# povduino.net
KiCad netlist of a schematic drawn in EAGLE
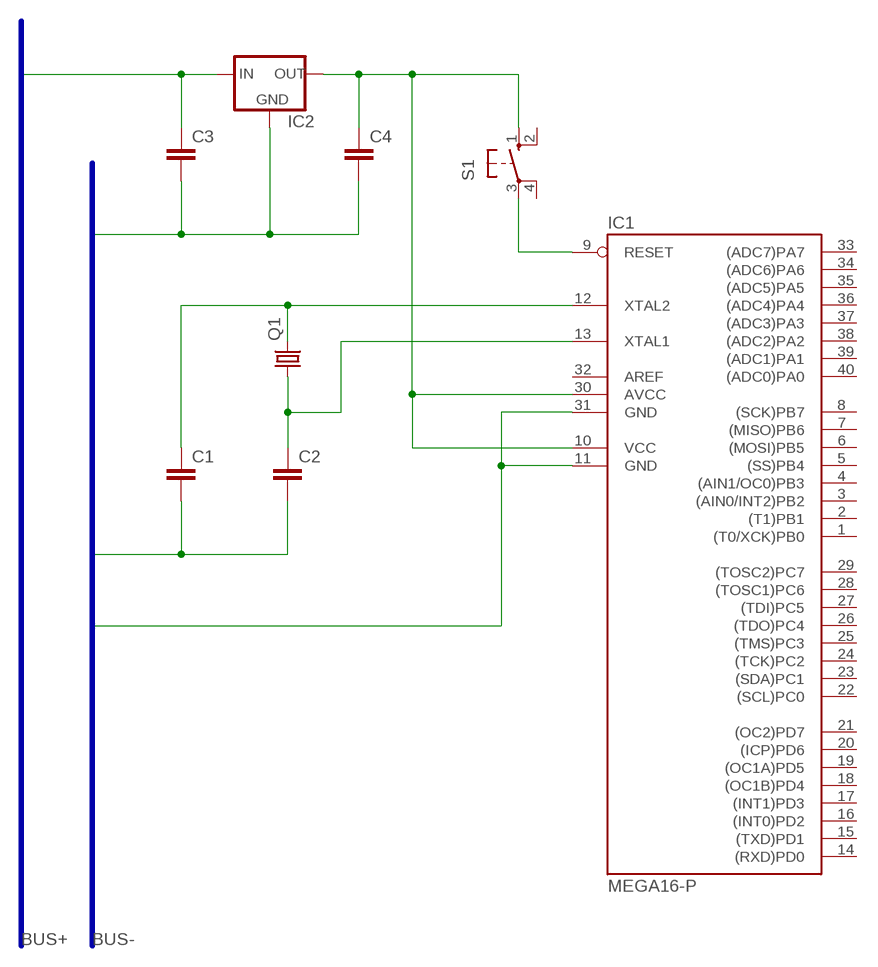
[diagram p0: schematic, sheet 1]

(export (version "E")
  (design (tool "Eeschema 10.0.6"))
  (components
    (comp (ref "C1")
      (value "C-EU025-025X050")
      (footprint "eagle-import:C025-025X050")
      (libsource (lib "eagle-import") (part "C-EU025-025X050"))
    )
    (comp (ref "C2")
      (value "C-EU025-025X050")
      (footprint "eagle-import:C025-025X050")
      (libsource (lib "eagle-import") (part "C-EU025-025X050"))
    )
    (comp (ref "C3")
      (value "C-EU025-025X050")
      (footprint "eagle-import:C025-025X050")
      (libsource (lib "eagle-import") (part "C-EU025-025X050"))
    )
    (comp (ref "C4")
      (value "C-EU025-025X050")
      (footprint "eagle-import:C025-025X050")
      (libsource (lib "eagle-import") (part "C-EU025-025X050"))
    )
    (comp (ref "IC1")
      (value "MEGA16-P")
      (footprint "eagle-import:DIL40")
      (fields (field (name "MPN") "ATMEGA16-16PU"))
      (libsource (lib "eagle-import") (part "MEGA16-P"))
    )
    (comp (ref "IC2")
      (value "78XXL")
      (footprint "eagle-import:78XXL")
      (libsource (lib "eagle-import") (part "78XXL"))
    )
    (comp (ref "Q1")
      (value "CRYSTALHC49S")
      (footprint "eagle-import:HC49_S")
      (libsource (lib "eagle-import") (part "CRYSTALHC49S"))
    )
    (comp (ref "S1")
      (value "10-XX")
      (footprint "eagle-import:B3F-10XX")
      (fields (field (name "MPN") "B3F-1000"))
      (libsource (lib "eagle-import") (part "10-XX"))
    )
  )
  (nets
    (net (code "1") (name "/BUS+") (class "Default")
      (node (ref "C3") (pin "1") (pinfunction "1_1") (pintype "passive"))
      (node (ref "C4") (pin "1") (pinfunction "1_1") (pintype "passive"))
      (node (ref "IC1") (pin "10") (pinfunction "VCC_10") (pintype "power_in"))
      (node (ref "IC1") (pin "30") (pinfunction "AVCC_30") (pintype "power_in"))
      (node (ref "IC2") (pin "IN") (pinfunction "IN_IN") (pintype "input"))
      (node (ref "IC2") (pin "OUT") (pinfunction "OUT_OUT") (pintype "passive"))
      (node (ref "S1") (pin "1") (pinfunction "S_1") (pintype "passive"))
    )
    (net (code "2") (name "/BUS-") (class "Default")
      (node (ref "C3") (pin "2") (pinfunction "2_2") (pintype "passive"))
      (node (ref "C4") (pin "2") (pinfunction "2_2") (pintype "passive"))
      (node (ref "IC1") (pin "11") (pinfunction "GND_11") (pintype "power_in"))
      (node (ref "IC1") (pin "31") (pinfunction "GND_31") (pintype "power_in"))
      (node (ref "IC2") (pin "GND") (pinfunction "GND_GND") (pintype "input"))
    )
    (net (code "5") (name "Net-(C1-Pad2)") (class "Default")
      (node (ref "C1") (pin "2") (pinfunction "2_2") (pintype "passive"))
      (node (ref "C2") (pin "2") (pinfunction "2_2") (pintype "passive"))
    )
    (net (code "6") (name "Net-(IC1-RESET)") (class "Default")
      (node (ref "IC1") (pin "9") (pinfunction "RESET_9") (pintype "input"))
      (node (ref "S1") (pin "3") (pinfunction "P_3") (pintype "passive"))
    )
    (net (code "7") (name "Net-(IC1-XTAL1)") (class "Default")
      (node (ref "C2") (pin "1") (pinfunction "1_1") (pintype "passive"))
      (node (ref "IC1") (pin "13") (pinfunction "XTAL1_13") (pintype "bidirectional"))
      (node (ref "Q1") (pin "1") (pinfunction "1_1") (pintype "passive"))
    )
    (net (code "8") (name "Net-(IC1-XTAL2)") (class "Default")
      (node (ref "C1") (pin "1") (pinfunction "1_1") (pintype "passive"))
      (node (ref "IC1") (pin "12") (pinfunction "XTAL2_12") (pintype "bidirectional"))
      (node (ref "Q1") (pin "2") (pinfunction "2_2") (pintype "passive"))
    )
    (net (code "9") (name "unconnected-(IC1-(ADC0)PA0-Pad40)") (class "Default")
      (node (ref "IC1") (pin "40") (pinfunction "(ADC0)PA0_40") (pintype "bidirectional"))
    )
    (net (code "10") (name "unconnected-(IC1-(ADC1)PA1-Pad39)") (class "Default")
      (node (ref "IC1") (pin "39") (pinfunction "(ADC1)PA1_39") (pintype "bidirectional"))
    )
    (net (code "11") (name "unconnected-(IC1-(ADC2)PA2-Pad38)") (class "Default")
      (node (ref "IC1") (pin "38") (pinfunction "(ADC2)PA2_38") (pintype "bidirectional"))
    )
    (net (code "12") (name "unconnected-(IC1-(ADC3)PA3-Pad37)") (class "Default")
      (node (ref "IC1") (pin "37") (pinfunction "(ADC3)PA3_37") (pintype "bidirectional"))
    )
    (net (code "13") (name "unconnected-(IC1-(ADC4)PA4-Pad36)") (class "Default")
      (node (ref "IC1") (pin "36") (pinfunction "(ADC4)PA4_36") (pintype "bidirectional"))
    )
    (net (code "14") (name "unconnected-(IC1-(ADC5)PA5-Pad35)") (class "Default")
      (node (ref "IC1") (pin "35") (pinfunction "(ADC5)PA5_35") (pintype "bidirectional"))
    )
    (net (code "15") (name "unconnected-(IC1-(ADC6)PA6-Pad34)") (class "Default")
      (node (ref "IC1") (pin "34") (pinfunction "(ADC6)PA6_34") (pintype "bidirectional"))
    )
    (net (code "16") (name "unconnected-(IC1-(ADC7)PA7-Pad33)") (class "Default")
      (node (ref "IC1") (pin "33") (pinfunction "(ADC7)PA7_33") (pintype "bidirectional"))
    )
    (net (code "17") (name "unconnected-(IC1-(AIN0{slash}INT2)PB2-Pad3)") (class "Default")
      (node (ref "IC1") (pin "3") (pinfunction "(AIN0/INT2)PB2_3") (pintype "bidirectional"))
    )
    (net (code "18") (name "unconnected-(IC1-(AIN1{slash}OC0)PB3-Pad4)") (class "Default")
      (node (ref "IC1") (pin "4") (pinfunction "(AIN1/OC0)PB3_4") (pintype "bidirectional"))
    )
    (net (code "19") (name "unconnected-(IC1-(ICP)PD6-Pad20)") (class "Default")
      (node (ref "IC1") (pin "20") (pinfunction "(ICP)PD6_20") (pintype "bidirectional"))
    )
    (net (code "20") (name "unconnected-(IC1-(INT0)PD2-Pad16)") (class "Default")
      (node (ref "IC1") (pin "16") (pinfunction "(INT0)PD2_16") (pintype "bidirectional"))
    )
    (net (code "21") (name "unconnected-(IC1-(INT1)PD3-Pad17)") (class "Default")
      (node (ref "IC1") (pin "17") (pinfunction "(INT1)PD3_17") (pintype "bidirectional"))
    )
    (net (code "22") (name "unconnected-(IC1-(MISO)PB6-Pad7)") (class "Default")
      (node (ref "IC1") (pin "7") (pinfunction "(MISO)PB6_7") (pintype "bidirectional"))
    )
    (net (code "23") (name "unconnected-(IC1-(MOSI)PB5-Pad6)") (class "Default")
      (node (ref "IC1") (pin "6") (pinfunction "(MOSI)PB5_6") (pintype "bidirectional"))
    )
    (net (code "24") (name "unconnected-(IC1-(OC1A)PD5-Pad19)") (class "Default")
      (node (ref "IC1") (pin "19") (pinfunction "(OC1A)PD5_19") (pintype "bidirectional"))
    )
    (net (code "25") (name "unconnected-(IC1-(OC1B)PD4-Pad18)") (class "Default")
      (node (ref "IC1") (pin "18") (pinfunction "(OC1B)PD4_18") (pintype "bidirectional"))
    )
    (net (code "26") (name "unconnected-(IC1-(OC2)PD7-Pad21)") (class "Default")
      (node (ref "IC1") (pin "21") (pinfunction "(OC2)PD7_21") (pintype "bidirectional"))
    )
    (net (code "27") (name "unconnected-(IC1-(RXD)PD0-Pad14)") (class "Default")
      (node (ref "IC1") (pin "14") (pinfunction "(RXD)PD0_14") (pintype "bidirectional"))
    )
    (net (code "28") (name "unconnected-(IC1-(SCK)PB7-Pad8)") (class "Default")
      (node (ref "IC1") (pin "8") (pinfunction "(SCK)PB7_8") (pintype "bidirectional"))
    )
    (net (code "29") (name "unconnected-(IC1-(SCL)PC0-Pad22)") (class "Default")
      (node (ref "IC1") (pin "22") (pinfunction "(SCL)PC0_22") (pintype "bidirectional"))
    )
    (net (code "30") (name "unconnected-(IC1-(SDA)PC1-Pad23)") (class "Default")
      (node (ref "IC1") (pin "23") (pinfunction "(SDA)PC1_23") (pintype "bidirectional"))
    )
    (net (code "31") (name "unconnected-(IC1-(SS)PB4-Pad5)") (class "Default")
      (node (ref "IC1") (pin "5") (pinfunction "(SS)PB4_5") (pintype "bidirectional"))
    )
    (net (code "32") (name "unconnected-(IC1-(T0{slash}XCK)PB0-Pad1)") (class "Default")
      (node (ref "IC1") (pin "1") (pinfunction "(T0/XCK)PB0_1") (pintype "bidirectional"))
    )
    (net (code "33") (name "unconnected-(IC1-(T1)PB1-Pad2)") (class "Default")
      (node (ref "IC1") (pin "2") (pinfunction "(T1)PB1_2") (pintype "bidirectional"))
    )
    (net (code "34") (name "unconnected-(IC1-(TCK)PC2-Pad24)") (class "Default")
      (node (ref "IC1") (pin "24") (pinfunction "(TCK)PC2_24") (pintype "bidirectional"))
    )
    (net (code "35") (name "unconnected-(IC1-(TDI)PC5-Pad27)") (class "Default")
      (node (ref "IC1") (pin "27") (pinfunction "(TDI)PC5_27") (pintype "bidirectional"))
    )
    (net (code "36") (name "unconnected-(IC1-(TDO)PC4-Pad26)") (class "Default")
      (node (ref "IC1") (pin "26") (pinfunction "(TDO)PC4_26") (pintype "bidirectional"))
    )
    (net (code "37") (name "unconnected-(IC1-(TMS)PC3-Pad25)") (class "Default")
      (node (ref "IC1") (pin "25") (pinfunction "(TMS)PC3_25") (pintype "bidirectional"))
    )
    (net (code "38") (name "unconnected-(IC1-(TOSC1)PC6-Pad28)") (class "Default")
      (node (ref "IC1") (pin "28") (pinfunction "(TOSC1)PC6_28") (pintype "bidirectional"))
    )
    (net (code "39") (name "unconnected-(IC1-(TOSC2)PC7-Pad29)") (class "Default")
      (node (ref "IC1") (pin "29") (pinfunction "(TOSC2)PC7_29") (pintype "bidirectional"))
    )
    (net (code "40") (name "unconnected-(IC1-(TXD)PD1-Pad15)") (class "Default")
      (node (ref "IC1") (pin "15") (pinfunction "(TXD)PD1_15") (pintype "bidirectional"))
    )
    (net (code "41") (name "unconnected-(IC1-AREF-Pad32)") (class "Default")
      (node (ref "IC1") (pin "32") (pinfunction "AREF_32") (pintype "passive"))
    )
    (net (code "42") (name "unconnected-(S1-P1-Pad4)") (class "Default")
      (node (ref "S1") (pin "4") (pinfunction "P1_4") (pintype "passive"))
    )
    (net (code "43") (name "unconnected-(S1-S1-Pad2)") (class "Default")
      (node (ref "S1") (pin "2") (pinfunction "S1_2") (pintype "passive"))
    )
  )
)
